# Sensor_Platform_GPIO_3v_boost_v2_1.net
KiCad netlist of a schematic drawn in EAGLE
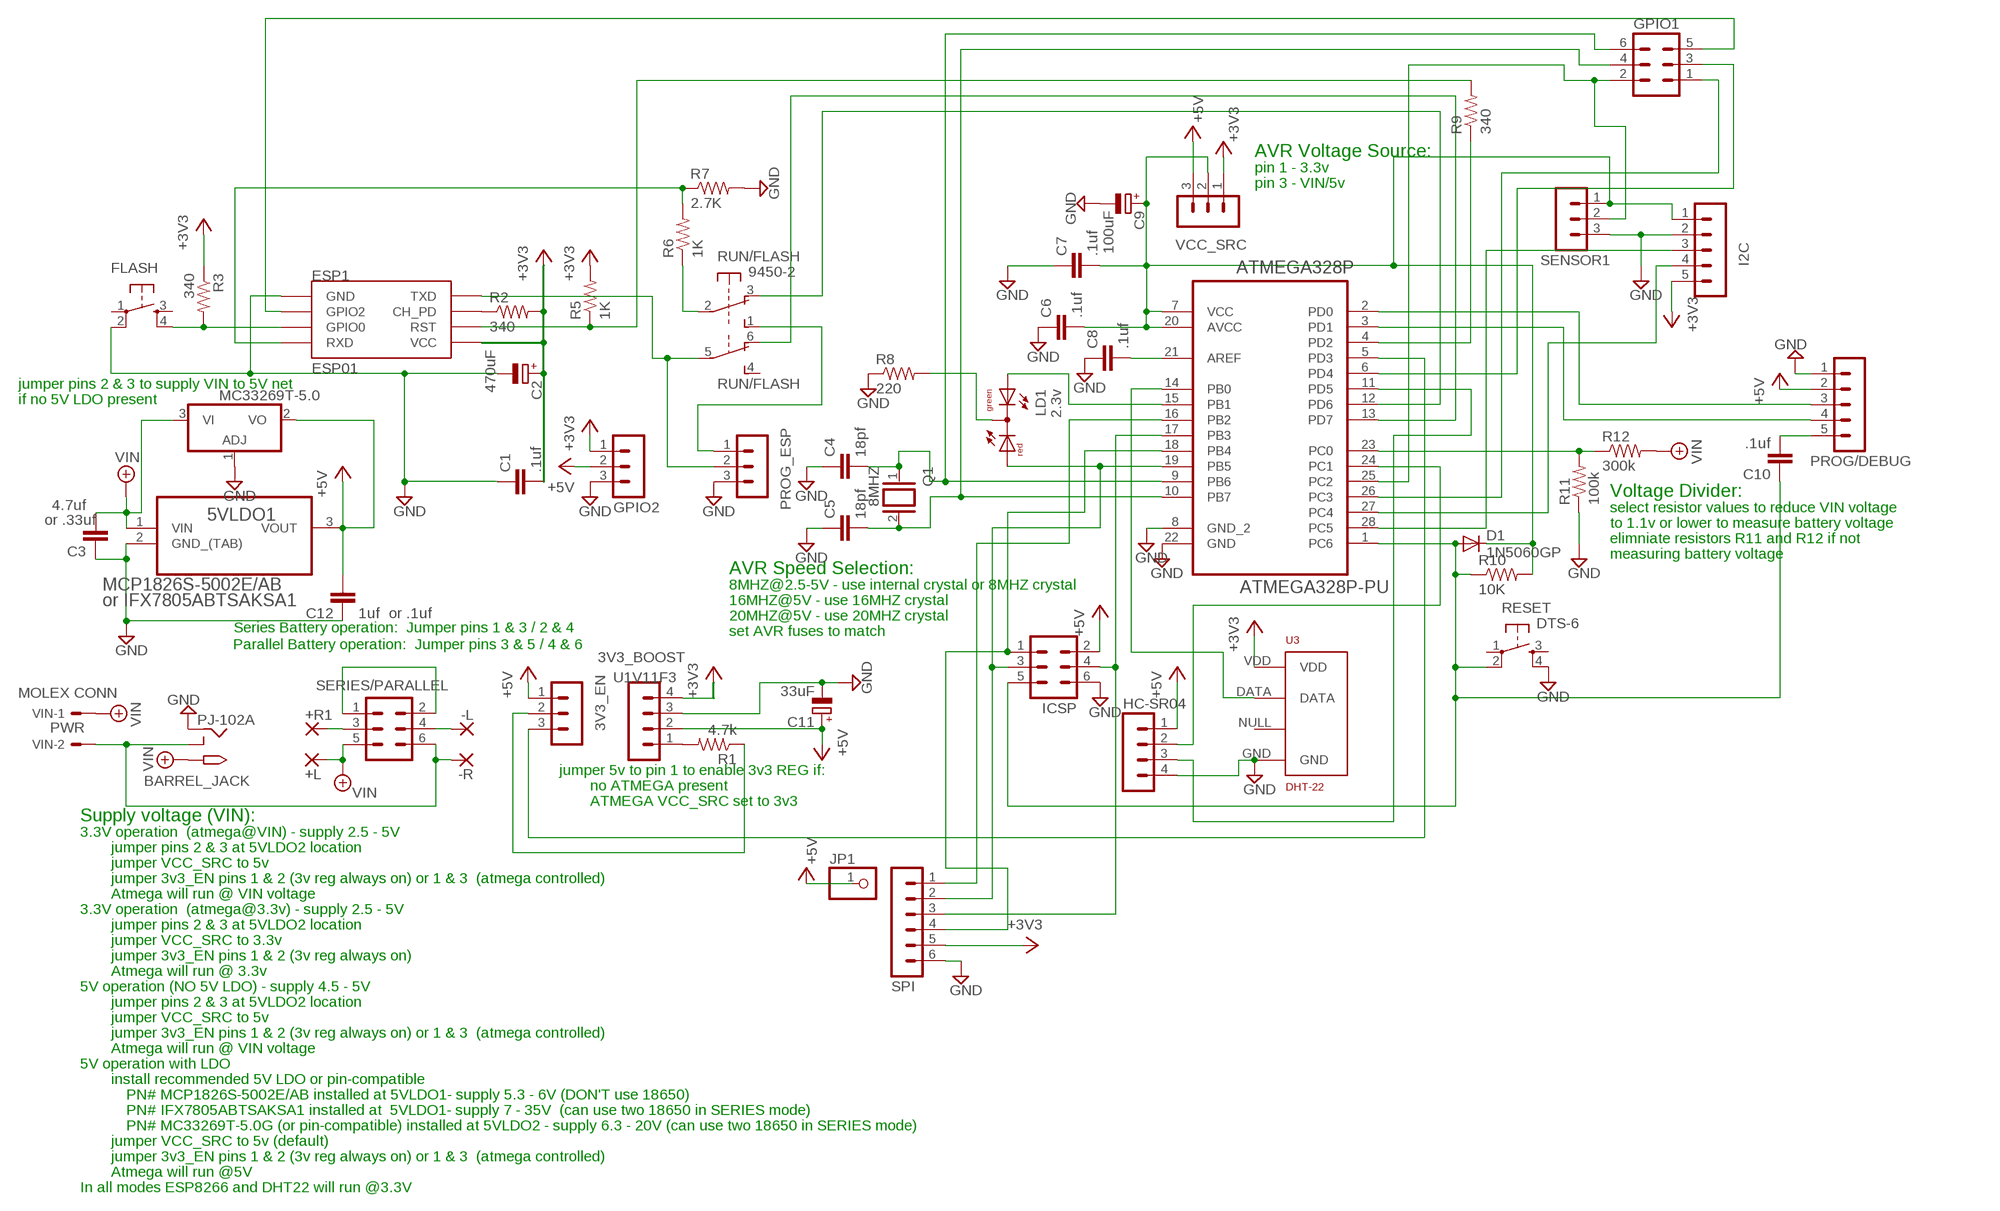
[diagram p0: schematic, sheet 1]

(export (version "E")
  (design (tool "Eeschema 10.0.6"))
  (components
    (comp (ref "+L")
      (value "WIREPADSMD2,54-5,08")
      (footprint "eagle-import:SMD2,54-5,08")
      (libsource (lib "eagle-import") (part "WIREPADSMD2,54-5,08"))
    )
    (comp (ref "+R1")
      (value "WIREPADSMD2,54-5,08")
      (footprint "eagle-import:SMD2,54-5,08")
      (libsource (lib "eagle-import") (part "WIREPADSMD2,54-5,08"))
    )
    (comp (ref "-L")
      (value "WIREPADSMD2,54-5,08")
      (footprint "eagle-import:SMD2,54-5,08")
      (libsource (lib "eagle-import") (part "WIREPADSMD2,54-5,08"))
    )
    (comp (ref "-R")
      (value "WIREPADSMD2,54-5,08")
      (footprint "eagle-import:SMD2,54-5,08")
      (libsource (lib "eagle-import") (part "WIREPADSMD2,54-5,08"))
    )
    (comp (ref "3V3_BOOST")
      (value "U1V11F3")
      (footprint "eagle-import:MA04-1")
      (libsource (lib "eagle-import") (part "MA04-1"))
    )
    (comp (ref "3V3_EN")
      (value "MA03-1")
      (footprint "eagle-import:MA03-1")
      (libsource (lib "eagle-import") (part "MA03-1"))
    )
    (comp (ref "5VLDO1")
      (value "MCP1826S-5002E/AB")
      (footprint "eagle-import:TO254P482X1024X3124-3P")
      (libsource (lib "eagle-import") (part "MCP1826S-5002E/AB"))
    )
    (comp (ref "5VLDO2")
      (value "MC33269T-5.0")
      (footprint "eagle-import:TO220V")
      (libsource (lib "eagle-import") (part "MC33269?T-5.0"))
    )
    (comp (ref "ATMEGA328P")
      (value "ATMEGA328P-PU")
      (footprint "eagle-import:DIP254P762X457-28")
      (libsource (lib "eagle-import") (part "ATMEGA328P-PU"))
    )
    (comp (ref "BARREL_JACK")
      (value "2.1MMJACKTHM")
      (footprint "eagle-import:PJ-102A")
      (libsource (lib "eagle-import") (part "2.1MMJACKTHM"))
    )
    (comp (ref "C1")
      (value ".1uf")
      (footprint "eagle-import:C2.5-2")
      (libsource (lib "eagle-import") (part "C2.5/2"))
    )
    (comp (ref "C2")
      (value "470uF")
      (footprint "eagle-import:E2,5-6E")
      (libsource (lib "eagle-import") (part "CPOL-EUE2,5-6E"))
    )
    (comp (ref "C3")
      (value "4.7uf")
      (footprint "eagle-import:C2.5-2")
      (libsource (lib "eagle-import") (part "C2.5/2"))
    )
    (comp (ref "C4")
      (value "18pf")
      (footprint "eagle-import:C2.5-2")
      (libsource (lib "eagle-import") (part "C2.5/2"))
    )
    (comp (ref "C5")
      (value "18pf")
      (footprint "eagle-import:C2.5-2")
      (libsource (lib "eagle-import") (part "C2.5/2"))
    )
    (comp (ref "C6")
      (value ".1uf")
      (footprint "eagle-import:C2.5-2")
      (libsource (lib "eagle-import") (part "C2.5/2"))
    )
    (comp (ref "C7")
      (value ".1uf")
      (footprint "eagle-import:C2.5-2")
      (libsource (lib "eagle-import") (part "C2.5/2"))
    )
    (comp (ref "C8")
      (value ".1uf")
      (footprint "eagle-import:C2.5-2")
      (libsource (lib "eagle-import") (part "C2.5/2"))
    )
    (comp (ref "C9")
      (value "100uF")
      (footprint "eagle-import:E2,5-6E")
      (libsource (lib "eagle-import") (part "CPOL-EUE2,5-6E"))
    )
    (comp (ref "C10")
      (value ".1uf")
      (footprint "eagle-import:C2.5-2")
      (libsource (lib "eagle-import") (part "C2.5/2"))
    )
    (comp (ref "C11")
      (value "33uF")
      (footprint "eagle-import:E2,5-6E")
      (libsource (lib "eagle-import") (part "CPOL-EUE2,5-6E"))
    )
    (comp (ref "C12")
      (value "1uf")
      (footprint "eagle-import:C2.5-2")
      (libsource (lib "eagle-import") (part "C2.5/2"))
    )
    (comp (ref "D1")
      (value "1N5060GP")
      (footprint "eagle-import:DO15-12")
      (libsource (lib "eagle-import") (part "1N5060GP"))
    )
    (comp (ref "ESP1")
      (value "ESP01")
      (footprint "eagle-import:ESP01")
      (libsource (lib "eagle-import") (part "ESP01"))
    )
    (comp (ref "FLASH")
      (value "DTS-6")
      (footprint "eagle-import:DTS-6")
      (libsource (lib "eagle-import") (part "DTS-6"))
    )
    (comp (ref "GPIO1")
      (value "MA03-2")
      (footprint "eagle-import:MA03-2")
      (libsource (lib "eagle-import") (part "MA03-2"))
    )
    (comp (ref "GPIO2")
      (value "MA03-1")
      (footprint "eagle-import:MA03-1")
      (libsource (lib "eagle-import") (part "MA03-1"))
    )
    (comp (ref "HC-SR04")
      (value "HC-SR04")
      (footprint "eagle-import:MA04-1")
      (libsource (lib "eagle-import") (part "MA04-1"))
    )
    (comp (ref "I2C")
      (value "MA05-1")
      (footprint "eagle-import:MA05-1")
      (libsource (lib "eagle-import") (part "MA05-1"))
    )
    (comp (ref "ICSP")
      (value "MA03-2")
      (footprint "eagle-import:MA03-2")
      (libsource (lib "eagle-import") (part "MA03-2"))
    )
    (comp (ref "JP1")
      (value "PINHD-1X1")
      (footprint "eagle-import:1X01")
      (libsource (lib "eagle-import") (part "PINHD-1X1"))
    )
    (comp (ref "LD1")
      (value "2.3v")
      (footprint "eagle-import:DUOLED-C-5MM")
      (libsource (lib "eagle-import") (part "DUOLED-RG-C"))
    )
    (comp (ref "PROG/DEBUG")
      (value "MA05-1")
      (footprint "eagle-import:MA05-1")
      (libsource (lib "eagle-import") (part "MA05-1"))
    )
    (comp (ref "PROG_ESP")
      (value "MA03-1")
      (footprint "eagle-import:MA03-1")
      (libsource (lib "eagle-import") (part "MA03-1"))
    )
    (comp (ref "Q1")
      (value "8MHZ")
      (footprint "eagle-import:QS")
      (libsource (lib "eagle-import") (part "XTAL/S"))
    )
    (comp (ref "R1")
      (value "4.7k")
      (footprint "eagle-import:0207_7")
      (libsource (lib "eagle-import") (part "R-US_0207/7"))
    )
    (comp (ref "R2")
      (value "340")
      (footprint "eagle-import:0207_7")
      (libsource (lib "eagle-import") (part "R-US_0207/7"))
    )
    (comp (ref "R3")
      (value "340")
      (footprint "eagle-import:0207_7")
      (libsource (lib "eagle-import") (part "R-US_0207/7"))
    )
    (comp (ref "R5")
      (value "1K")
      (footprint "eagle-import:0207_7")
      (libsource (lib "eagle-import") (part "R-US_0207/7"))
    )
    (comp (ref "R6")
      (value "1K")
      (footprint "eagle-import:0207_7")
      (libsource (lib "eagle-import") (part "R-US_0207/7"))
    )
    (comp (ref "R7")
      (value "2.7K")
      (footprint "eagle-import:0207_7")
      (libsource (lib "eagle-import") (part "R-US_0207/7"))
    )
    (comp (ref "R8")
      (value "220")
      (footprint "eagle-import:0207_7")
      (libsource (lib "eagle-import") (part "R-US_0207/7"))
    )
    (comp (ref "R9")
      (value "340")
      (footprint "eagle-import:0207_7")
      (libsource (lib "eagle-import") (part "R-US_0207/7"))
    )
    (comp (ref "R10")
      (value "10K")
      (footprint "eagle-import:0207_7")
      (libsource (lib "eagle-import") (part "R-US_0207/7"))
    )
    (comp (ref "R11")
      (value "100k")
      (footprint "eagle-import:0207_7")
      (libsource (lib "eagle-import") (part "R-US_0207/7"))
    )
    (comp (ref "R12")
      (value "300k")
      (footprint "eagle-import:0207_7")
      (libsource (lib "eagle-import") (part "R-US_0207/7"))
    )
    (comp (ref "RESET")
      (value "DTS-6")
      (footprint "eagle-import:DTS-6")
      (libsource (lib "eagle-import") (part "DTS-6"))
    )
    (comp (ref "RUN/FLASH")
      (value "9450-2")
      (footprint "eagle-import:9450-2")
      (libsource (lib "eagle-import") (part "9450-2"))
    )
    (comp (ref "SENSOR1")
      (value "MA03-1")
      (footprint "eagle-import:MA03-1")
      (libsource (lib "eagle-import") (part "MA03-1"))
    )
    (comp (ref "SERIES/PARALLEL")
      (value "MA03-2")
      (footprint "eagle-import:MA03-2")
      (libsource (lib "eagle-import") (part "MA03-2"))
    )
    (comp (ref "SPI")
      (value "MA06-1")
      (footprint "eagle-import:MA06-1")
      (libsource (lib "eagle-import") (part "MA06-1"))
    )
    (comp (ref "U3")
      (value "DHT-22")
      (footprint "eagle-import:RHT03_DHT-22")
      (libsource (lib "eagle-import") (part "RHT03_DHT-22_AM2302"))
    )
    (comp (ref "VCC_SRC")
      (value "MA03-1")
      (footprint "eagle-import:MA03-1")
      (libsource (lib "eagle-import") (part "MA03-1"))
    )
    (comp (ref "VIN")
      (value "PWR")
      (footprint "eagle-import:6410-02")
      (libsource (lib "eagle-import") (part "22-?-0227-2021"))
    )
  )
  (nets
    (net (code "1") (name "+3V3") (class "Default")
      (node (ref "3V3_BOOST") (pin "4") (pinfunction "4_4") (pintype "passive"))
      (node (ref "C1") (pin "2") (pinfunction "2_2") (pintype "passive"))
      (node (ref "C2") (pin "+") (pinfunction "+_+") (pintype "passive"))
      (node (ref "ESP1") (pin "VCC") (pinfunction "VCC_VCC") (pintype "bidirectional"))
      (node (ref "GPIO2") (pin "1") (pinfunction "1_1") (pintype "passive"))
      (node (ref "I2C") (pin "5") (pinfunction "5_5") (pintype "passive"))
      (node (ref "R2") (pin "2") (pinfunction "2_2") (pintype "passive"))
      (node (ref "R3") (pin "1") (pinfunction "1_1") (pintype "passive"))
      (node (ref "R5") (pin "2") (pinfunction "2_2") (pintype "passive"))
      (node (ref "SPI") (pin "5") (pinfunction "5_5") (pintype "passive"))
      (node (ref "U3") (pin "VDD") (pinfunction "VDD_VDD") (pintype "power_in"))
      (node (ref "VCC_SRC") (pin "1") (pinfunction "1_1") (pintype "passive"))
    )
    (net (code "2") (name "+5V") (class "Default")
      (node (ref "3V3_BOOST") (pin "2") (pinfunction "2_2") (pintype "passive"))
      (node (ref "3V3_EN") (pin "1") (pinfunction "1_1") (pintype "passive"))
      (node (ref "5VLDO1") (pin "3") (pinfunction "VOUT_3") (pintype "output"))
      (node (ref "5VLDO2") (pin "2") (pinfunction "VO_2") (pintype "passive"))
      (node (ref "C11") (pin "+") (pinfunction "+_+") (pintype "passive"))
      (node (ref "C12") (pin "2") (pinfunction "2_2") (pintype "passive"))
      (node (ref "GPIO2") (pin "2") (pinfunction "2_2") (pintype "passive"))
      (node (ref "HC-SR04") (pin "1") (pinfunction "1_1") (pintype "passive"))
      (node (ref "ICSP") (pin "2") (pinfunction "2_2") (pintype "passive"))
      (node (ref "JP1") (pin "1") (pinfunction "1_1") (pintype "passive"))
      (node (ref "PROG/DEBUG") (pin "2") (pinfunction "2_2") (pintype "passive"))
      (node (ref "VCC_SRC") (pin "3") (pinfunction "3_3") (pintype "passive"))
    )
    (net (code "3") (name "GND") (class "Default")
      (node (ref "3V3_BOOST") (pin "3") (pinfunction "3_3") (pintype "passive"))
      (node (ref "5VLDO1") (pin "2") (pinfunction "GND_(TAB)_2") (pintype "passive"))
      (node (ref "5VLDO2") (pin "1") (pinfunction "ADJ_1") (pintype "input"))
      (node (ref "ATMEGA328P") (pin "22") (pinfunction "GND_22") (pintype "passive"))
      (node (ref "ATMEGA328P") (pin "8") (pinfunction "GND_2_8") (pintype "passive"))
      (node (ref "BARREL_JACK") (pin "RING") (pinfunction "RING_RING") (pintype "bidirectional"))
      (node (ref "C1") (pin "1") (pinfunction "1_1") (pintype "passive"))
      (node (ref "C11") (pin "-") (pinfunction "-_-") (pintype "passive"))
      (node (ref "C12") (pin "1") (pinfunction "1_1") (pintype "passive"))
      (node (ref "C2") (pin "-") (pinfunction "-_-") (pintype "passive"))
      (node (ref "C3") (pin "1") (pinfunction "1_1") (pintype "passive"))
      (node (ref "C4") (pin "1") (pinfunction "1_1") (pintype "passive"))
      (node (ref "C5") (pin "1") (pinfunction "1_1") (pintype "passive"))
      (node (ref "C6") (pin "1") (pinfunction "1_1") (pintype "passive"))
      (node (ref "C7") (pin "1") (pinfunction "1_1") (pintype "passive"))
      (node (ref "C8") (pin "1") (pinfunction "1_1") (pintype "passive"))
      (node (ref "C9") (pin "-") (pinfunction "-_-") (pintype "passive"))
      (node (ref "ESP1") (pin "GND") (pinfunction "GND_GND") (pintype "bidirectional"))
      (node (ref "FLASH") (pin "2") (pinfunction "2_2") (pintype "passive"))
      (node (ref "GPIO2") (pin "3") (pinfunction "3_3") (pintype "passive"))
      (node (ref "HC-SR04") (pin "4") (pinfunction "4_4") (pintype "passive"))
      (node (ref "I2C") (pin "2") (pinfunction "2_2") (pintype "passive"))
      (node (ref "ICSP") (pin "6") (pinfunction "6_6") (pintype "passive"))
      (node (ref "PROG/DEBUG") (pin "1") (pinfunction "1_1") (pintype "passive"))
      (node (ref "PROG_ESP") (pin "3") (pinfunction "3_3") (pintype "passive"))
      (node (ref "R11") (pin "1") (pinfunction "1_1") (pintype "passive"))
      (node (ref "R7") (pin "2") (pinfunction "2_2") (pintype "passive"))
      (node (ref "R8") (pin "1") (pinfunction "1_1") (pintype "passive"))
      (node (ref "RESET") (pin "4") (pinfunction "4_4") (pintype "passive"))
      (node (ref "SENSOR1") (pin "3") (pinfunction "3_3") (pintype "passive"))
      (node (ref "SPI") (pin "6") (pinfunction "6_6") (pintype "passive"))
      (node (ref "U3") (pin "GND") (pinfunction "GND_GND") (pintype "power_in"))
    )
    (net (code "4") (name "Net-(+R1-P)") (class "Default")
      (node (ref "+R1") (pin "1") (pinfunction "P_1") (pintype "passive"))
      (node (ref "SERIES/PARALLEL") (pin "3") (pinfunction "3_3") (pintype "passive"))
    )
    (net (code "5") (name "Net-(-L-P)") (class "Default")
      (node (ref "-L") (pin "1") (pinfunction "P_1") (pintype "passive"))
      (node (ref "SERIES/PARALLEL") (pin "4") (pinfunction "4_4") (pintype "passive"))
    )
    (net (code "6") (name "Net-(-R-P)") (class "Default")
      (node (ref "-R") (pin "1") (pinfunction "P_1") (pintype "passive"))
      (node (ref "BARREL_JACK") (pin "RING_SW") (pinfunction "RING_SW_RING_SW") (pintype "bidirectional"))
      (node (ref "SERIES/PARALLEL") (pin "6") (pinfunction "6_6") (pintype "passive"))
      (node (ref "VIN") (pin "2") (pinfunction "S_2") (pintype "passive"))
    )
    (net (code "7") (name "Net-(3V3_BOOST-Pad1)") (class "Default")
      (node (ref "3V3_BOOST") (pin "1") (pinfunction "1_1") (pintype "passive"))
      (node (ref "R1") (pin "2") (pinfunction "2_2") (pintype "passive"))
    )
    (net (code "8") (name "Net-(3V3_EN-Pad2)") (class "Default")
      (node (ref "3V3_EN") (pin "2") (pinfunction "2_2") (pintype "passive"))
      (node (ref "R1") (pin "1") (pinfunction "1_1") (pintype "passive"))
    )
    (net (code "9") (name "Net-(ATMEGA328P-AREF)") (class "Default")
      (node (ref "ATMEGA328P") (pin "21") (pinfunction "AREF_21") (pintype "input"))
      (node (ref "C8") (pin "2") (pinfunction "2_2") (pintype "passive"))
    )
    (net (code "10") (name "Net-(ATMEGA328P-AVCC)") (class "Default")
      (node (ref "ATMEGA328P") (pin "20") (pinfunction "AVCC_20") (pintype "power_in"))
      (node (ref "ATMEGA328P") (pin "7") (pinfunction "VCC_7") (pintype "power_in"))
      (node (ref "C6") (pin "2") (pinfunction "2_2") (pintype "passive"))
      (node (ref "C7") (pin "2") (pinfunction "2_2") (pintype "passive"))
      (node (ref "C9") (pin "+") (pinfunction "+_+") (pintype "passive"))
      (node (ref "D1") (pin "C") (pinfunction "C_C") (pintype "passive"))
      (node (ref "I2C") (pin "1") (pinfunction "1_1") (pintype "passive"))
      (node (ref "R10") (pin "2") (pinfunction "2_2") (pintype "passive"))
      (node (ref "SENSOR1") (pin "1") (pinfunction "1_1") (pintype "passive"))
      (node (ref "VCC_SRC") (pin "2") (pinfunction "2_2") (pintype "passive"))
    )
    (net (code "11") (name "Net-(ATMEGA328P-PB0)") (class "Default")
      (node (ref "ATMEGA328P") (pin "14") (pinfunction "PB0_14") (pintype "bidirectional"))
      (node (ref "U3") (pin "DATA") (pinfunction "DATA_DATA") (pintype "bidirectional"))
    )
    (net (code "12") (name "Net-(ATMEGA328P-PB1)") (class "Default")
      (node (ref "ATMEGA328P") (pin "15") (pinfunction "PB1_15") (pintype "bidirectional"))
      (node (ref "LD1") (pin "AX") (pinfunction "AG_AX") (pintype "passive"))
    )
    (net (code "13") (name "Net-(ATMEGA328P-PB2)") (class "Default")
      (node (ref "ATMEGA328P") (pin "16") (pinfunction "PB2_16") (pintype "bidirectional"))
      (node (ref "SPI") (pin "1") (pinfunction "1_1") (pintype "passive"))
    )
    (net (code "14") (name "Net-(ATMEGA328P-PB3)") (class "Default")
      (node (ref "ATMEGA328P") (pin "17") (pinfunction "PB3_17") (pintype "bidirectional"))
      (node (ref "ICSP") (pin "4") (pinfunction "4_4") (pintype "passive"))
      (node (ref "SPI") (pin "3") (pinfunction "3_3") (pintype "passive"))
    )
    (net (code "15") (name "Net-(ATMEGA328P-PB4)") (class "Default")
      (node (ref "ATMEGA328P") (pin "18") (pinfunction "PB4_18") (pintype "bidirectional"))
      (node (ref "ICSP") (pin "1") (pinfunction "1_1") (pintype "passive"))
      (node (ref "SPI") (pin "4") (pinfunction "4_4") (pintype "passive"))
    )
    (net (code "16") (name "Net-(ATMEGA328P-PB5)") (class "Default")
      (node (ref "ATMEGA328P") (pin "19") (pinfunction "PB5_19") (pintype "bidirectional"))
      (node (ref "ICSP") (pin "3") (pinfunction "3_3") (pintype "passive"))
      (node (ref "LD1") (pin "AR") (pinfunction "AR_AR") (pintype "passive"))
      (node (ref "SPI") (pin "2") (pinfunction "2_2") (pintype "passive"))
    )
    (net (code "17") (name "Net-(ATMEGA328P-PB6)") (class "Default")
      (node (ref "ATMEGA328P") (pin "9") (pinfunction "PB6_9") (pintype "bidirectional"))
      (node (ref "C4") (pin "2") (pinfunction "2_2") (pintype "passive"))
      (node (ref "GPIO1") (pin "6") (pinfunction "6_6") (pintype "passive"))
      (node (ref "Q1") (pin "1") (pinfunction "1_1") (pintype "passive"))
    )
    (net (code "18") (name "Net-(ATMEGA328P-PB7)") (class "Default")
      (node (ref "ATMEGA328P") (pin "10") (pinfunction "PB7_10") (pintype "bidirectional"))
      (node (ref "C5") (pin "2") (pinfunction "2_2") (pintype "passive"))
      (node (ref "GPIO1") (pin "4") (pinfunction "4_4") (pintype "passive"))
      (node (ref "Q1") (pin "2") (pinfunction "2_2") (pintype "passive"))
    )
    (net (code "19") (name "Net-(ATMEGA328P-PC0)") (class "Default")
      (node (ref "ATMEGA328P") (pin "23") (pinfunction "PC0_23") (pintype "bidirectional"))
      (node (ref "R11") (pin "2") (pinfunction "2_2") (pintype "passive"))
      (node (ref "R12") (pin "1") (pinfunction "1_1") (pintype "passive"))
    )
    (net (code "20") (name "Net-(ATMEGA328P-PC1)") (class "Default")
      (node (ref "ATMEGA328P") (pin "24") (pinfunction "PC1_24") (pintype "bidirectional"))
      (node (ref "HC-SR04") (pin "2") (pinfunction "2_2") (pintype "passive"))
    )
    (net (code "21") (name "Net-(ATMEGA328P-PC2)") (class "Default")
      (node (ref "ATMEGA328P") (pin "25") (pinfunction "PC2_25") (pintype "bidirectional"))
      (node (ref "GPIO1") (pin "2") (pinfunction "2_2") (pintype "passive"))
      (node (ref "SENSOR1") (pin "2") (pinfunction "2_2") (pintype "passive"))
    )
    (net (code "22") (name "Net-(ATMEGA328P-PC3)") (class "Default")
      (node (ref "ATMEGA328P") (pin "26") (pinfunction "PC3_26") (pintype "bidirectional"))
      (node (ref "GPIO1") (pin "1") (pinfunction "1_1") (pintype "passive"))
    )
    (net (code "23") (name "Net-(ATMEGA328P-PC4)") (class "Default")
      (node (ref "ATMEGA328P") (pin "27") (pinfunction "PC4_27") (pintype "bidirectional"))
      (node (ref "I2C") (pin "4") (pinfunction "4_4") (pintype "passive"))
    )
    (net (code "24") (name "Net-(ATMEGA328P-PC5)") (class "Default")
      (node (ref "ATMEGA328P") (pin "28") (pinfunction "PC5_28") (pintype "bidirectional"))
      (node (ref "I2C") (pin "3") (pinfunction "3_3") (pintype "passive"))
    )
    (net (code "25") (name "Net-(ATMEGA328P-PC6)") (class "Default")
      (node (ref "ATMEGA328P") (pin "1") (pinfunction "PC6_1") (pintype "bidirectional"))
      (node (ref "C10") (pin "1") (pinfunction "1_1") (pintype "passive"))
      (node (ref "D1") (pin "A") (pinfunction "A_A") (pintype "passive"))
      (node (ref "ICSP") (pin "5") (pinfunction "5_5") (pintype "passive"))
      (node (ref "R10") (pin "1") (pinfunction "1_1") (pintype "passive"))
      (node (ref "RESET") (pin "2") (pinfunction "2_2") (pintype "passive"))
    )
    (net (code "26") (name "Net-(ATMEGA328P-PD0)") (class "Default")
      (node (ref "ATMEGA328P") (pin "2") (pinfunction "PD0_2") (pintype "bidirectional"))
      (node (ref "PROG/DEBUG") (pin "3") (pinfunction "3_3") (pintype "passive"))
    )
    (net (code "27") (name "Net-(ATMEGA328P-PD1)") (class "Default")
      (node (ref "ATMEGA328P") (pin "3") (pinfunction "PD1_3") (pintype "bidirectional"))
      (node (ref "PROG/DEBUG") (pin "4") (pinfunction "4_4") (pintype "passive"))
    )
    (net (code "28") (name "Net-(ATMEGA328P-PD2)") (class "Default")
      (node (ref "ATMEGA328P") (pin "4") (pinfunction "PD2_4") (pintype "bidirectional"))
      (node (ref "R9") (pin "1") (pinfunction "1_1") (pintype "passive"))
    )
    (net (code "29") (name "Net-(ATMEGA328P-PD3)") (class "Default")
      (node (ref "3V3_EN") (pin "3") (pinfunction "3_3") (pintype "passive"))
      (node (ref "ATMEGA328P") (pin "5") (pinfunction "PD3_5") (pintype "bidirectional"))
    )
    (net (code "30") (name "Net-(ATMEGA328P-PD4)") (class "Default")
      (node (ref "ATMEGA328P") (pin "6") (pinfunction "PD4_6") (pintype "bidirectional"))
      (node (ref "GPIO1") (pin "3") (pinfunction "3_3") (pintype "passive"))
    )
    (net (code "31") (name "Net-(ATMEGA328P-PD5)") (class "Default")
      (node (ref "ATMEGA328P") (pin "11") (pinfunction "PD5_11") (pintype "bidirectional"))
      (node (ref "HC-SR04") (pin "3") (pinfunction "3_3") (pintype "passive"))
    )
    (net (code "32") (name "Net-(ATMEGA328P-PD6)") (class "Default")
      (node (ref "ATMEGA328P") (pin "12") (pinfunction "PD6_12") (pintype "bidirectional"))
      (node (ref "RUN/FLASH") (pin "3") (pinfunction "O_3") (pintype "passive"))
    )
    (net (code "33") (name "Net-(ATMEGA328P-PD7)") (class "Default")
      (node (ref "ATMEGA328P") (pin "13") (pinfunction "PD7_13") (pintype "bidirectional"))
      (node (ref "RUN/FLASH") (pin "6") (pinfunction "O_6") (pintype "passive"))
    )
    (net (code "34") (name "Net-(C10-Pad2)") (class "Default")
      (node (ref "C10") (pin "2") (pinfunction "2_2") (pintype "passive"))
      (node (ref "PROG/DEBUG") (pin "5") (pinfunction "5_5") (pintype "passive"))
    )
    (net (code "35") (name "Net-(ESP1-PadCH_PD)") (class "Default")
      (node (ref "ESP1") (pin "CH_PD") (pinfunction "CH_PD_CH_PD") (pintype "bidirectional"))
      (node (ref "R2") (pin "1") (pinfunction "1_1") (pintype "passive"))
    )
    (net (code "36") (name "Net-(ESP1-PadGPIO0)") (class "Default")
      (node (ref "ESP1") (pin "GPIO0") (pinfunction "GPIO0_GPIO0") (pintype "bidirectional"))
      (node (ref "FLASH") (pin "4") (pinfunction "4_4") (pintype "passive"))
      (node (ref "R3") (pin "2") (pinfunction "2_2") (pintype "passive"))
    )
    (net (code "37") (name "Net-(ESP1-PadGPIO2)") (class "Default")
      (node (ref "ESP1") (pin "GPIO2") (pinfunction "GPIO2_GPIO2") (pintype "bidirectional"))
      (node (ref "GPIO1") (pin "5") (pinfunction "5_5") (pintype "passive"))
    )
    (net (code "38") (name "Net-(ESP1-PadRST)") (class "Default")
      (node (ref "ESP1") (pin "RST") (pinfunction "RST_RST") (pintype "bidirectional"))
      (node (ref "R5") (pin "1") (pinfunction "1_1") (pintype "passive"))
      (node (ref "R9") (pin "2") (pinfunction "2_2") (pintype "passive"))
    )
    (net (code "39") (name "Net-(ESP1-RXD)") (class "Default")
      (node (ref "ESP1") (pin "RX") (pinfunction "RXD_RX") (pintype "bidirectional"))
      (node (ref "R6") (pin "2") (pinfunction "2_2") (pintype "passive"))
      (node (ref "R7") (pin "1") (pinfunction "1_1") (pintype "passive"))
    )
    (net (code "40") (name "Net-(ESP1-TXD)") (class "Default")
      (node (ref "ESP1") (pin "TX") (pinfunction "TXD_TX") (pintype "bidirectional"))
      (node (ref "PROG_ESP") (pin "2") (pinfunction "2_2") (pintype "passive"))
      (node (ref "RUN/FLASH") (pin "5") (pinfunction "P_5") (pintype "passive"))
    )
    (net (code "41") (name "Net-(LD1-PadC)") (class "Default")
      (node (ref "LD1") (pin "C") (pinfunction "C_C") (pintype "passive"))
      (node (ref "R8") (pin "2") (pinfunction "2_2") (pintype "passive"))
    )
    (net (code "42") (name "Net-(RUN/FLASHA-P)") (class "Default")
      (node (ref "R6") (pin "1") (pinfunction "1_1") (pintype "passive"))
      (node (ref "RUN/FLASH") (pin "2") (pinfunction "P_2") (pintype "passive"))
    )
    (net (code "43") (name "Net-(RUN/FLASHA-S)") (class "Default")
      (node (ref "PROG_ESP") (pin "1") (pinfunction "1_1") (pintype "passive"))
      (node (ref "RUN/FLASH") (pin "1") (pinfunction "S_1") (pintype "passive"))
    )
    (net (code "44") (name "Net-(SERIES/PARALLEL-Pad1)") (class "Default")
      (node (ref "SERIES/PARALLEL") (pin "1") (pinfunction "1_1") (pintype "passive"))
      (node (ref "SERIES/PARALLEL") (pin "2") (pinfunction "2_2") (pintype "passive"))
    )
    (net (code "45") (name "VIN") (class "Default")
      (node (ref "+L") (pin "1") (pinfunction "P_1") (pintype "passive"))
      (node (ref "5VLDO1") (pin "1") (pinfunction "VIN_1") (pintype "input"))
      (node (ref "5VLDO2") (pin "3") (pinfunction "VI_3") (pintype "input"))
      (node (ref "BARREL_JACK") (pin "TIP") (pinfunction "TIP_TIP") (pintype "bidirectional"))
      (node (ref "C3") (pin "2") (pinfunction "2_2") (pintype "passive"))
      (node (ref "R12") (pin "2") (pinfunction "2_2") (pintype "passive"))
      (node (ref "SERIES/PARALLEL") (pin "5") (pinfunction "5_5") (pintype "passive"))
      (node (ref "VIN") (pin "1") (pinfunction "S_1") (pintype "passive"))
    )
    (net (code "46") (name "unconnected-(FLASH-Pad1)") (class "Default")
      (node (ref "FLASH") (pin "1") (pinfunction "1_1") (pintype "passive"))
    )
    (net (code "47") (name "unconnected-(FLASH-Pad3)") (class "Default")
      (node (ref "FLASH") (pin "3") (pinfunction "3_3") (pintype "passive"))
    )
    (net (code "48") (name "unconnected-(RESET-Pad1)") (class "Default")
      (node (ref "RESET") (pin "1") (pinfunction "1_1") (pintype "passive"))
    )
    (net (code "49") (name "unconnected-(RESET-Pad3)") (class "Default")
      (node (ref "RESET") (pin "3") (pinfunction "3_3") (pintype "passive"))
    )
    (net (code "50") (name "unconnected-(RUN/FLASHB-S-Pad4)") (class "Default")
      (node (ref "RUN/FLASH") (pin "4") (pinfunction "S_4") (pintype "passive"))
    )
    (net (code "51") (name "unconnected-(U3-PadNULL)") (class "Default")
      (node (ref "U3") (pin "NULL") (pinfunction "NULL_NULL") (pintype "no_connect"))
    )
  )
)
